# shield_ard.net
KiCad netlist of a schematic drawn in EAGLE
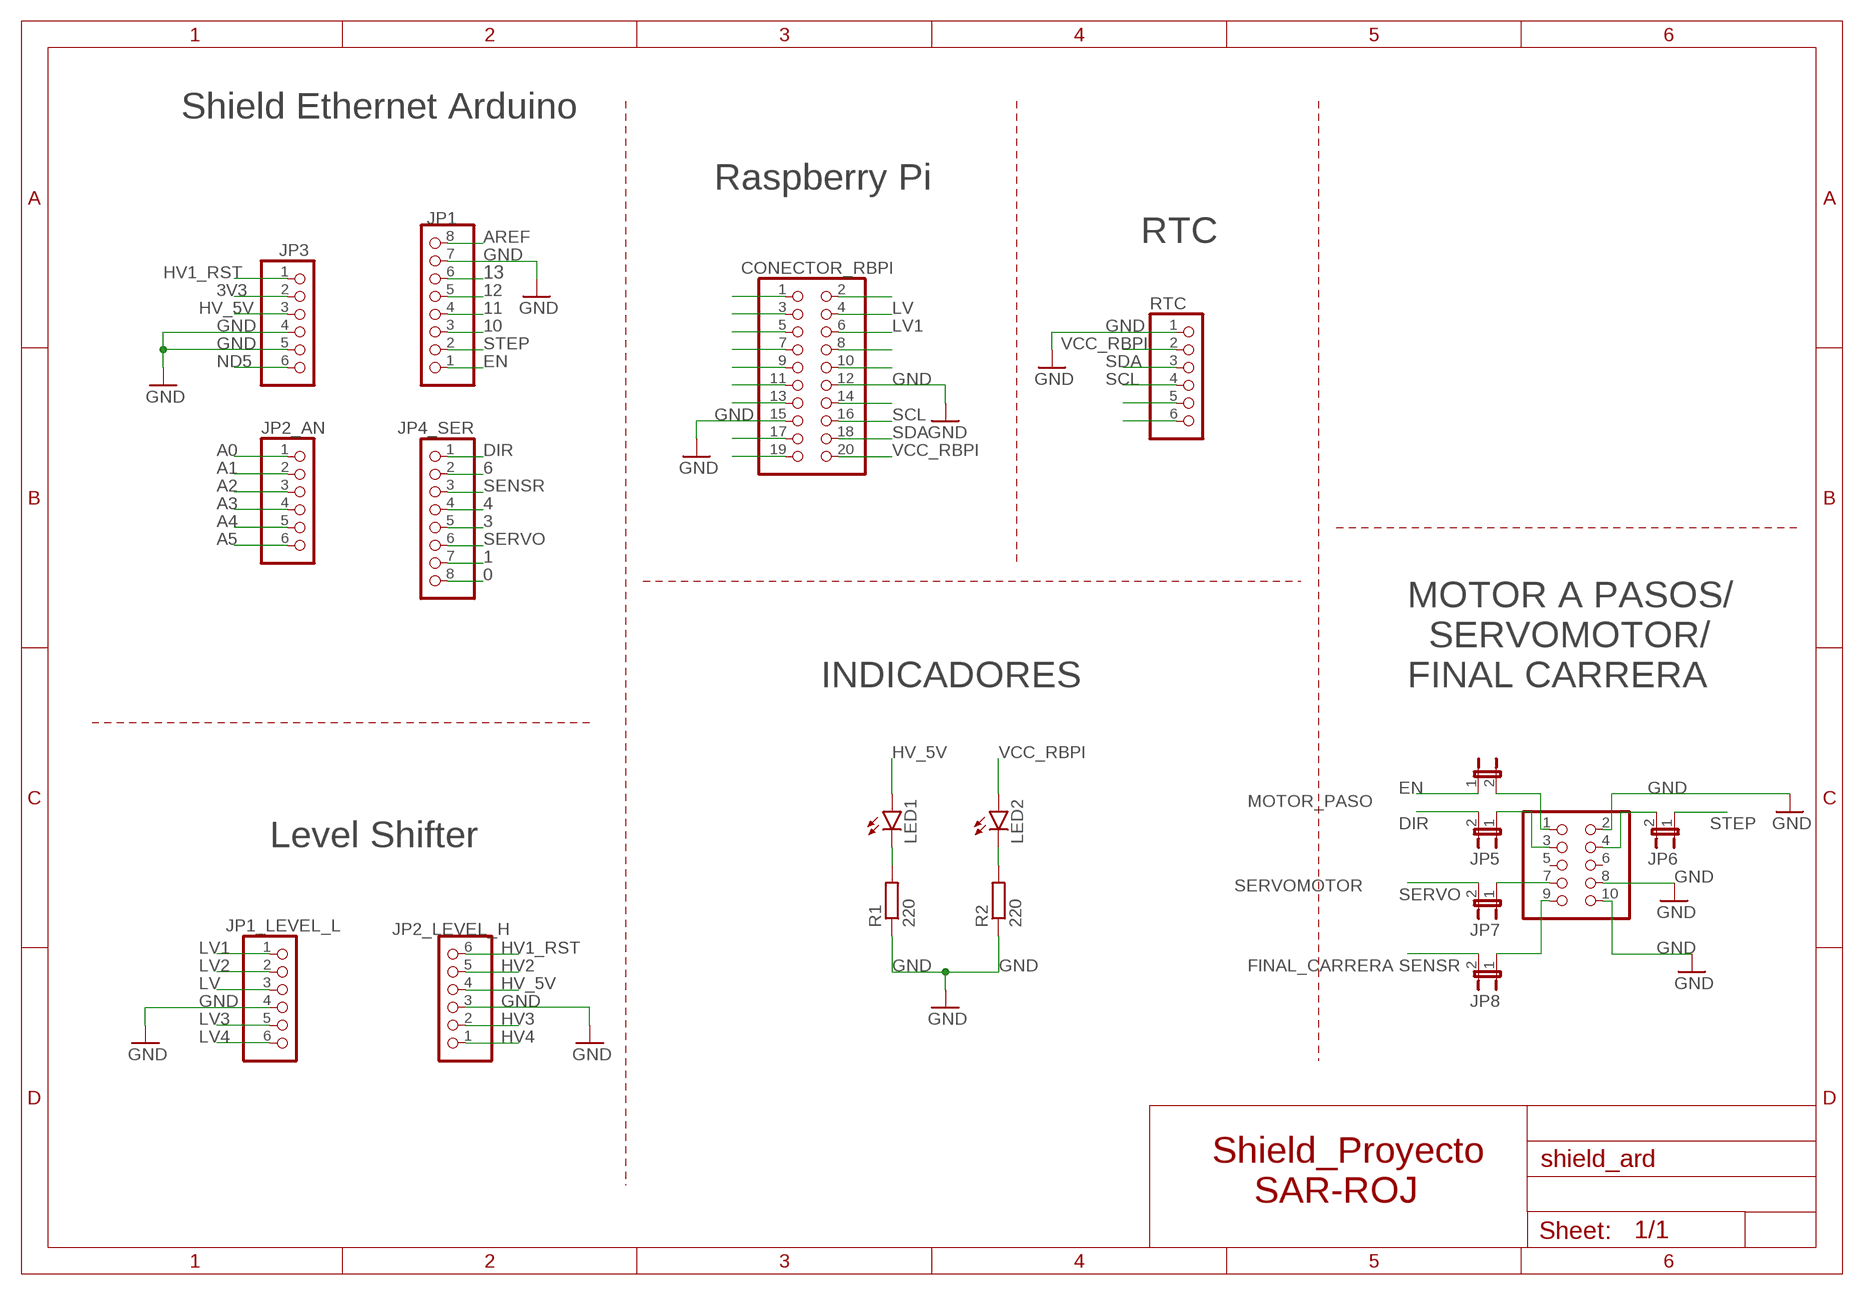
[diagram p0: schematic, sheet 1]

(export (version "E")
  (design (tool "Eeschema 10.0.6"))
  (components
    (comp (ref "CONECTOR_RBPI")
      (value "PINHD-2X10")
      (footprint "eagle-import:2X10")
      (libsource (lib "eagle-import") (part "PINHD-2X10"))
    )
    (comp (ref "JP1")
      (value "PINHD-1X8")
      (footprint "eagle-import:1X08")
      (libsource (lib "eagle-import") (part "PINHD-1X8"))
    )
    (comp (ref "JP1_LEVEL_L")
      (value "PINHD-1X6")
      (footprint "eagle-import:1X06")
      (libsource (lib "eagle-import") (part "PINHD-1X6"))
    )
    (comp (ref "JP2")
      (value "JUMPER-2PTH")
      (footprint "eagle-import:1X02")
      (libsource (lib "eagle-import") (part "JUMPER-2PTH"))
    )
    (comp (ref "JP2_AN")
      (value "PINHD-1X6")
      (footprint "eagle-import:1X06")
      (libsource (lib "eagle-import") (part "PINHD-1X6"))
    )
    (comp (ref "JP2_LEVEL_H")
      (value "PINHD-1X6")
      (footprint "eagle-import:1X06")
      (libsource (lib "eagle-import") (part "PINHD-1X6"))
    )
    (comp (ref "JP3")
      (value "PINHD-1X6")
      (footprint "eagle-import:1X06")
      (libsource (lib "eagle-import") (part "PINHD-1X6"))
    )
    (comp (ref "JP4_SER")
      (value "PINHD-1X8")
      (footprint "eagle-import:1X08")
      (libsource (lib "eagle-import") (part "PINHD-1X8"))
    )
    (comp (ref "JP5")
      (value "JUMPER-2PTH")
      (footprint "eagle-import:1X02")
      (libsource (lib "eagle-import") (part "JUMPER-2PTH"))
    )
    (comp (ref "JP6")
      (value "JUMPER-2PTH")
      (footprint "eagle-import:1X02")
      (libsource (lib "eagle-import") (part "JUMPER-2PTH"))
    )
    (comp (ref "JP7")
      (value "JUMPER-2PTH")
      (footprint "eagle-import:1X02")
      (libsource (lib "eagle-import") (part "JUMPER-2PTH"))
    )
    (comp (ref "JP8")
      (value "JUMPER-2PTH")
      (footprint "eagle-import:1X02")
      (libsource (lib "eagle-import") (part "JUMPER-2PTH"))
    )
    (comp (ref "LED1")
      (value "LEDCHIP-LED0805")
      (footprint "eagle-import:CHIP-LED0805")
      (libsource (lib "eagle-import") (part "LEDCHIP-LED0805"))
    )
    (comp (ref "LED2")
      (value "LEDCHIP-LED0805")
      (footprint "eagle-import:CHIP-LED0805")
      (libsource (lib "eagle-import") (part "LEDCHIP-LED0805"))
    )
    (comp (ref "MOTOR_PASO")
      (value "PINHD-2X5")
      (footprint "eagle-import:2X05")
      (libsource (lib "eagle-import") (part "PINHD-2X5"))
    )
    (comp (ref "R1")
      (value "220")
      (footprint "eagle-import:R0805")
      (libsource (lib "eagle-import") (part "R-EU_R0805"))
    )
    (comp (ref "R2")
      (value "220")
      (footprint "eagle-import:R0805")
      (libsource (lib "eagle-import") (part "R-EU_R0805"))
    )
    (comp (ref "RTC")
      (value "PINHD-1X6/90")
      (footprint "eagle-import:1X06_90")
      (libsource (lib "eagle-import") (part "PINHD-1X6/90"))
    )
  )
  (nets
    (net (code "1") (name "/0") (class "Default")
      (node (ref "JP4_SER") (pin "8") (pinfunction "8_8") (pintype "passive"))
    )
    (net (code "2") (name "/1") (class "Default")
      (node (ref "JP4_SER") (pin "7") (pinfunction "7_7") (pintype "passive"))
    )
    (net (code "3") (name "/3") (class "Default")
      (node (ref "JP4_SER") (pin "5") (pinfunction "5_5") (pintype "passive"))
    )
    (net (code "4") (name "/3V3") (class "Default")
      (node (ref "JP3") (pin "2") (pinfunction "2_2") (pintype "passive"))
    )
    (net (code "5") (name "/4") (class "Default")
      (node (ref "JP4_SER") (pin "4") (pinfunction "4_4") (pintype "passive"))
    )
    (net (code "6") (name "/6") (class "Default")
      (node (ref "JP4_SER") (pin "2") (pinfunction "2_2") (pintype "passive"))
    )
    (net (code "7") (name "/10") (class "Default")
      (node (ref "JP1") (pin "3") (pinfunction "3_3") (pintype "passive"))
    )
    (net (code "8") (name "/11") (class "Default")
      (node (ref "JP1") (pin "4") (pinfunction "4_4") (pintype "passive"))
    )
    (net (code "9") (name "/12") (class "Default")
      (node (ref "JP1") (pin "5") (pinfunction "5_5") (pintype "passive"))
    )
    (net (code "10") (name "/13") (class "Default")
      (node (ref "JP1") (pin "6") (pinfunction "6_6") (pintype "passive"))
    )
    (net (code "11") (name "/A0") (class "Default")
      (node (ref "JP2_AN") (pin "1") (pinfunction "1_1") (pintype "passive"))
    )
    (net (code "12") (name "/A1") (class "Default")
      (node (ref "JP2_AN") (pin "2") (pinfunction "2_2") (pintype "passive"))
    )
    (net (code "13") (name "/A2") (class "Default")
      (node (ref "JP2_AN") (pin "3") (pinfunction "3_3") (pintype "passive"))
    )
    (net (code "14") (name "/A3") (class "Default")
      (node (ref "JP2_AN") (pin "4") (pinfunction "4_4") (pintype "passive"))
    )
    (net (code "15") (name "/A4") (class "Default")
      (node (ref "JP2_AN") (pin "5") (pinfunction "5_5") (pintype "passive"))
    )
    (net (code "16") (name "/A5") (class "Default")
      (node (ref "JP2_AN") (pin "6") (pinfunction "6_6") (pintype "passive"))
    )
    (net (code "17") (name "/AREF") (class "Default")
      (node (ref "JP1") (pin "8") (pinfunction "8_8") (pintype "passive"))
    )
    (net (code "18") (name "/DIR") (class "Default")
      (node (ref "JP4_SER") (pin "1") (pinfunction "1_1") (pintype "passive"))
      (node (ref "JP5") (pin "1") (pinfunction "1_1") (pintype "passive"))
      (node (ref "JP5") (pin "2") (pinfunction "2_2") (pintype "passive"))
      (node (ref "MOTOR_PASO") (pin "3") (pinfunction "3_3") (pintype "passive"))
    )
    (net (code "19") (name "/EN") (class "Default")
      (node (ref "JP1") (pin "1") (pinfunction "1_1") (pintype "passive"))
      (node (ref "JP2") (pin "1") (pinfunction "1_1") (pintype "passive"))
      (node (ref "JP2") (pin "2") (pinfunction "2_2") (pintype "passive"))
      (node (ref "MOTOR_PASO") (pin "1") (pinfunction "1_1") (pintype "passive"))
    )
    (net (code "20") (name "/HV1_RST") (class "Default")
      (node (ref "JP2_LEVEL_H") (pin "6") (pinfunction "6_6") (pintype "passive"))
      (node (ref "JP3") (pin "1") (pinfunction "1_1") (pintype "passive"))
    )
    (net (code "21") (name "/HV2") (class "Default")
      (node (ref "JP2_LEVEL_H") (pin "5") (pinfunction "5_5") (pintype "passive"))
    )
    (net (code "22") (name "/HV3") (class "Default")
      (node (ref "JP2_LEVEL_H") (pin "2") (pinfunction "2_2") (pintype "passive"))
    )
    (net (code "23") (name "/HV4") (class "Default")
      (node (ref "JP2_LEVEL_H") (pin "1") (pinfunction "1_1") (pintype "passive"))
    )
    (net (code "24") (name "/HV_5V") (class "Default")
      (node (ref "JP2_LEVEL_H") (pin "4") (pinfunction "4_4") (pintype "passive"))
      (node (ref "JP3") (pin "3") (pinfunction "3_3") (pintype "passive"))
      (node (ref "LED1") (pin "A") (pinfunction "A_A") (pintype "passive"))
    )
    (net (code "25") (name "/LV") (class "Default")
      (node (ref "CONECTOR_RBPI") (pin "4") (pinfunction "4_4") (pintype "passive"))
      (node (ref "JP1_LEVEL_L") (pin "3") (pinfunction "3_3") (pintype "passive"))
    )
    (net (code "26") (name "/LV1") (class "Default")
      (node (ref "CONECTOR_RBPI") (pin "6") (pinfunction "6_6") (pintype "passive"))
      (node (ref "JP1_LEVEL_L") (pin "1") (pinfunction "1_1") (pintype "passive"))
    )
    (net (code "27") (name "/LV2") (class "Default")
      (node (ref "JP1_LEVEL_L") (pin "2") (pinfunction "2_2") (pintype "passive"))
    )
    (net (code "28") (name "/LV3") (class "Default")
      (node (ref "JP1_LEVEL_L") (pin "5") (pinfunction "5_5") (pintype "passive"))
    )
    (net (code "29") (name "/LV4") (class "Default")
      (node (ref "JP1_LEVEL_L") (pin "6") (pinfunction "6_6") (pintype "passive"))
    )
    (net (code "30") (name "/ND5") (class "Default")
      (node (ref "JP3") (pin "6") (pinfunction "6_6") (pintype "passive"))
    )
    (net (code "31") (name "/SCL") (class "Default")
      (node (ref "CONECTOR_RBPI") (pin "16") (pinfunction "16_16") (pintype "passive"))
      (node (ref "RTC") (pin "4") (pinfunction "4_4") (pintype "passive"))
    )
    (net (code "32") (name "/SDA") (class "Default")
      (node (ref "CONECTOR_RBPI") (pin "18") (pinfunction "18_18") (pintype "passive"))
      (node (ref "RTC") (pin "3") (pinfunction "3_3") (pintype "passive"))
    )
    (net (code "33") (name "/SENSR") (class "Default")
      (node (ref "JP4_SER") (pin "3") (pinfunction "3_3") (pintype "passive"))
      (node (ref "JP8") (pin "1") (pinfunction "1_1") (pintype "passive"))
      (node (ref "JP8") (pin "2") (pinfunction "2_2") (pintype "passive"))
      (node (ref "MOTOR_PASO") (pin "9") (pinfunction "9_9") (pintype "passive"))
    )
    (net (code "34") (name "/SERVO") (class "Default")
      (node (ref "JP4_SER") (pin "6") (pinfunction "6_6") (pintype "passive"))
      (node (ref "JP7") (pin "2") (pinfunction "2_2") (pintype "passive"))
    )
    (net (code "35") (name "/STEP") (class "Default")
      (node (ref "JP1") (pin "2") (pinfunction "2_2") (pintype "passive"))
      (node (ref "JP6") (pin "1") (pinfunction "1_1") (pintype "passive"))
    )
    (net (code "36") (name "/VCC_RBPI") (class "Default")
      (node (ref "CONECTOR_RBPI") (pin "20") (pinfunction "20_20") (pintype "passive"))
      (node (ref "LED2") (pin "A") (pinfunction "A_A") (pintype "passive"))
      (node (ref "RTC") (pin "2") (pinfunction "2_2") (pintype "passive"))
    )
    (net (code "37") (name "GND") (class "Default")
      (node (ref "CONECTOR_RBPI") (pin "12") (pinfunction "12_12") (pintype "passive"))
      (node (ref "CONECTOR_RBPI") (pin "15") (pinfunction "15_15") (pintype "passive"))
      (node (ref "JP1") (pin "7") (pinfunction "7_7") (pintype "passive"))
      (node (ref "JP1_LEVEL_L") (pin "4") (pinfunction "4_4") (pintype "passive"))
      (node (ref "JP2_LEVEL_H") (pin "3") (pinfunction "3_3") (pintype "passive"))
      (node (ref "JP3") (pin "4") (pinfunction "4_4") (pintype "passive"))
      (node (ref "JP3") (pin "5") (pinfunction "5_5") (pintype "passive"))
      (node (ref "MOTOR_PASO") (pin "10") (pinfunction "10_10") (pintype "passive"))
      (node (ref "MOTOR_PASO") (pin "2") (pinfunction "2_2") (pintype "passive"))
      (node (ref "MOTOR_PASO") (pin "8") (pinfunction "8_8") (pintype "passive"))
      (node (ref "R1") (pin "1") (pinfunction "1_1") (pintype "passive"))
      (node (ref "R2") (pin "1") (pinfunction "1_1") (pintype "passive"))
      (node (ref "RTC") (pin "1") (pinfunction "1_1") (pintype "passive"))
    )
    (net (code "38") (name "Net-(JP6-Pad2)") (class "Default")
      (node (ref "JP6") (pin "2") (pinfunction "2_2") (pintype "passive"))
      (node (ref "MOTOR_PASO") (pin "4") (pinfunction "4_4") (pintype "passive"))
    )
    (net (code "39") (name "Net-(JP7-Pad1)") (class "Default")
      (node (ref "JP7") (pin "1") (pinfunction "1_1") (pintype "passive"))
      (node (ref "MOTOR_PASO") (pin "7") (pinfunction "7_7") (pintype "passive"))
    )
    (net (code "40") (name "Net-(LED1-PadC)") (class "Default")
      (node (ref "LED1") (pin "C") (pinfunction "C_C") (pintype "passive"))
      (node (ref "R1") (pin "2") (pinfunction "2_2") (pintype "passive"))
    )
    (net (code "41") (name "Net-(LED2-PadC)") (class "Default")
      (node (ref "LED2") (pin "C") (pinfunction "C_C") (pintype "passive"))
      (node (ref "R2") (pin "2") (pinfunction "2_2") (pintype "passive"))
    )
    (net (code "42") (name "unconnected-(CONECTOR_RBPI-Pad1)") (class "Default")
      (node (ref "CONECTOR_RBPI") (pin "1") (pinfunction "1_1") (pintype "passive"))
    )
    (net (code "43") (name "unconnected-(CONECTOR_RBPI-Pad2)") (class "Default")
      (node (ref "CONECTOR_RBPI") (pin "2") (pinfunction "2_2") (pintype "passive"))
    )
    (net (code "44") (name "unconnected-(CONECTOR_RBPI-Pad3)") (class "Default")
      (node (ref "CONECTOR_RBPI") (pin "3") (pinfunction "3_3") (pintype "passive"))
    )
    (net (code "45") (name "unconnected-(CONECTOR_RBPI-Pad5)") (class "Default")
      (node (ref "CONECTOR_RBPI") (pin "5") (pinfunction "5_5") (pintype "passive"))
    )
    (net (code "46") (name "unconnected-(CONECTOR_RBPI-Pad7)") (class "Default")
      (node (ref "CONECTOR_RBPI") (pin "7") (pinfunction "7_7") (pintype "passive"))
    )
    (net (code "47") (name "unconnected-(CONECTOR_RBPI-Pad8)") (class "Default")
      (node (ref "CONECTOR_RBPI") (pin "8") (pinfunction "8_8") (pintype "passive"))
    )
    (net (code "48") (name "unconnected-(CONECTOR_RBPI-Pad9)") (class "Default")
      (node (ref "CONECTOR_RBPI") (pin "9") (pinfunction "9_9") (pintype "passive"))
    )
    (net (code "49") (name "unconnected-(CONECTOR_RBPI-Pad10)") (class "Default")
      (node (ref "CONECTOR_RBPI") (pin "10") (pinfunction "10_10") (pintype "passive"))
    )
    (net (code "50") (name "unconnected-(CONECTOR_RBPI-Pad11)") (class "Default")
      (node (ref "CONECTOR_RBPI") (pin "11") (pinfunction "11_11") (pintype "passive"))
    )
    (net (code "51") (name "unconnected-(CONECTOR_RBPI-Pad13)") (class "Default")
      (node (ref "CONECTOR_RBPI") (pin "13") (pinfunction "13_13") (pintype "passive"))
    )
    (net (code "52") (name "unconnected-(CONECTOR_RBPI-Pad14)") (class "Default")
      (node (ref "CONECTOR_RBPI") (pin "14") (pinfunction "14_14") (pintype "passive"))
    )
    (net (code "53") (name "unconnected-(CONECTOR_RBPI-Pad17)") (class "Default")
      (node (ref "CONECTOR_RBPI") (pin "17") (pinfunction "17_17") (pintype "passive"))
    )
    (net (code "54") (name "unconnected-(CONECTOR_RBPI-Pad19)") (class "Default")
      (node (ref "CONECTOR_RBPI") (pin "19") (pinfunction "19_19") (pintype "passive"))
    )
    (net (code "55") (name "unconnected-(MOTOR_PASO-Pad5)") (class "Default")
      (node (ref "MOTOR_PASO") (pin "5") (pinfunction "5_5") (pintype "passive"))
    )
    (net (code "56") (name "unconnected-(MOTOR_PASO-Pad6)") (class "Default")
      (node (ref "MOTOR_PASO") (pin "6") (pinfunction "6_6") (pintype "passive"))
    )
    (net (code "57") (name "unconnected-(RTC-Pad5)") (class "Default")
      (node (ref "RTC") (pin "5") (pinfunction "5_5") (pintype "passive"))
    )
    (net (code "58") (name "unconnected-(RTC-Pad6)") (class "Default")
      (node (ref "RTC") (pin "6") (pinfunction "6_6") (pintype "passive"))
    )
  )
)
